# board.net
KiCad netlist of a schematic drawn in EAGLE
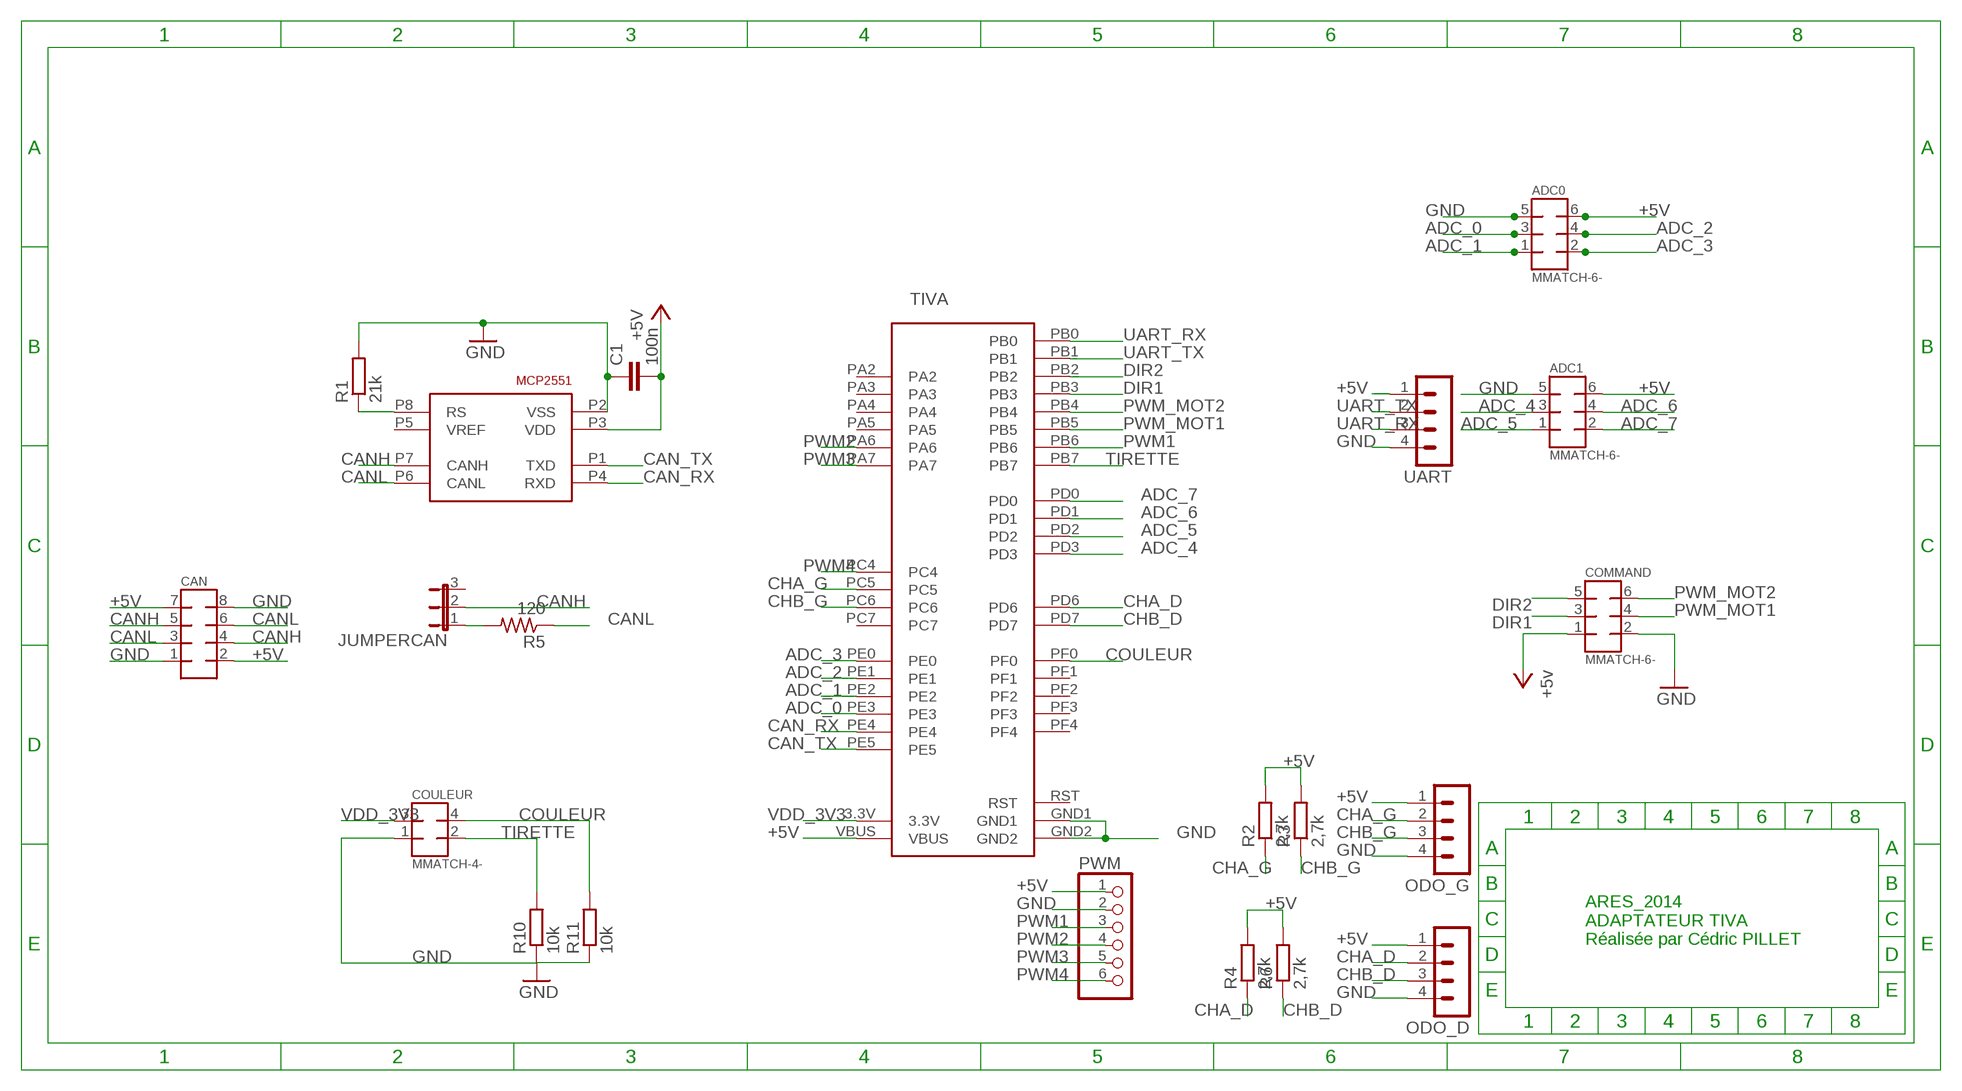
[diagram p0: schematic, sheet 1]

(export (version "E")
  (design (tool "Eeschema 10.0.6"))
  (components
    (comp (ref "ADC0")
      (value "MMATCH-6-")
      (footprint "eagle-import:AMP-215079-6")
      (libsource (lib "eagle-import") (part "MMATCH-6-"))
    )
    (comp (ref "ADC1")
      (value "MMATCH-6-")
      (footprint "eagle-import:AMP-215079-6")
      (libsource (lib "eagle-import") (part "MMATCH-6-"))
    )
    (comp (ref "C1")
      (value "100n")
      (footprint "eagle-import:C0805")
      (libsource (lib "eagle-import") (part "C-EUC0805"))
    )
    (comp (ref "CAN")
      (value "MMATCH-8-PTH")
      (footprint "eagle-import:AMP-215079-8")
      (libsource (lib "eagle-import") (part "MMATCH-8-PTH"))
    )
    (comp (ref "COMMAND")
      (value "MMATCH-6-")
      (footprint "eagle-import:AMP-215079-6")
      (libsource (lib "eagle-import") (part "MMATCH-6-"))
    )
    (comp (ref "COULEUR")
      (value "MMATCH-4-")
      (footprint "eagle-import:AMP-215079-4")
      (libsource (lib "eagle-import") (part "MMATCH-4-"))
    )
    (comp (ref "JUMPERCAN")
      (value "JP2W")
      (footprint "eagle-import:JP2W")
      (libsource (lib "eagle-import") (part "JP2W"))
    )
    (comp (ref "ODO_D")
      (value "MA04-1")
      (footprint "eagle-import:MA04-1")
      (libsource (lib "eagle-import") (part "MA04-1"))
    )
    (comp (ref "ODO_G")
      (value "MA04-1")
      (footprint "eagle-import:MA04-1")
      (libsource (lib "eagle-import") (part "MA04-1"))
    )
    (comp (ref "PWM")
      (value "PINHD-1X6/90")
      (footprint "eagle-import:1X06_90")
      (libsource (lib "eagle-import") (part "PINHD-1X6/90"))
    )
    (comp (ref "R1")
      (value "21k")
      (footprint "eagle-import:R0805")
      (libsource (lib "eagle-import") (part "R-EU_R0805"))
    )
    (comp (ref "R2")
      (value "2,7k")
      (footprint "eagle-import:R0805")
      (libsource (lib "eagle-import") (part "R-EU_R0805"))
    )
    (comp (ref "R3")
      (value "2,7k")
      (footprint "eagle-import:R0805")
      (libsource (lib "eagle-import") (part "R-EU_R0805"))
    )
    (comp (ref "R4")
      (value "2,7k")
      (footprint "eagle-import:R0805")
      (libsource (lib "eagle-import") (part "R-EU_R0805"))
    )
    (comp (ref "R5")
      (value "120")
      (footprint "eagle-import:M0805")
      (libsource (lib "eagle-import") (part "R-US_M0805"))
    )
    (comp (ref "R6")
      (value "2,7k")
      (footprint "eagle-import:R0805")
      (libsource (lib "eagle-import") (part "R-EU_R0805"))
    )
    (comp (ref "R10")
      (value "10k")
      (footprint "eagle-import:R0805")
      (libsource (lib "eagle-import") (part "R-EU_R0805"))
    )
    (comp (ref "R11")
      (value "10k")
      (footprint "eagle-import:R0805")
      (libsource (lib "eagle-import") (part "R-EU_R0805"))
    )
    (comp (ref "TIVA")
      (value "STELLARIS-LAUNCHPADSTELLARIS-LAUNCHPAD")
      (footprint "eagle-import:LAUNCHPAD-XL")
      (libsource (lib "eagle-import") (part "STELLARIS-LAUNCHPADSTELLARIS-LAUNCHPAD"))
    )
    (comp (ref "U$1")
      (value "MCP2551")
      (footprint "eagle-import:SOIC_8")
      (libsource (lib "eagle-import") (part "MCP2551"))
    )
    (comp (ref "UART")
      (value "MA04-1")
      (footprint "eagle-import:MA04-1")
      (libsource (lib "eagle-import") (part "MA04-1"))
    )
  )
  (nets
    (net (code "1") (name "+5V") (class "Default")
      (node (ref "ADC0") (pin "6") (pinfunction "8_6") (pintype "bidirectional"))
      (node (ref "ADC1") (pin "6") (pinfunction "8_6") (pintype "bidirectional"))
      (node (ref "C1") (pin "2") (pinfunction "2_2") (pintype "passive"))
      (node (ref "CAN") (pin "2") (pinfunction "2_2") (pintype "bidirectional"))
      (node (ref "CAN") (pin "7") (pinfunction "7_7") (pintype "bidirectional"))
      (node (ref "COMMAND") (pin "1") (pinfunction "3_1") (pintype "bidirectional"))
      (node (ref "ODO_D") (pin "1") (pinfunction "1_1") (pintype "passive"))
      (node (ref "ODO_G") (pin "1") (pinfunction "1_1") (pintype "passive"))
      (node (ref "PWM") (pin "1") (pinfunction "1_1") (pintype "passive"))
      (node (ref "R2") (pin "2") (pinfunction "2_2") (pintype "passive"))
      (node (ref "R3") (pin "2") (pinfunction "2_2") (pintype "passive"))
      (node (ref "R4") (pin "2") (pinfunction "2_2") (pintype "passive"))
      (node (ref "R6") (pin "2") (pinfunction "2_2") (pintype "passive"))
      (node (ref "TIVA") (pin "VBUS") (pinfunction "VBUS_VBUS") (pintype "power_in"))
      (node (ref "U$1") (pin "P3") (pinfunction "VDD_P3") (pintype "bidirectional"))
      (node (ref "UART") (pin "1") (pinfunction "1_1") (pintype "passive"))
    )
    (net (code "2") (name "/ADC_0") (class "Default")
      (node (ref "ADC0") (pin "3") (pinfunction "5_3") (pintype "bidirectional"))
      (node (ref "TIVA") (pin "PE3") (pinfunction "PE3_PE3") (pintype "bidirectional"))
    )
    (net (code "3") (name "/ADC_1") (class "Default")
      (node (ref "ADC0") (pin "1") (pinfunction "3_1") (pintype "bidirectional"))
      (node (ref "TIVA") (pin "PE2") (pinfunction "PE2_PE2") (pintype "bidirectional"))
    )
    (net (code "4") (name "/ADC_2") (class "Default")
      (node (ref "ADC0") (pin "4") (pinfunction "6_4") (pintype "bidirectional"))
      (node (ref "TIVA") (pin "PE1") (pinfunction "PE1_PE1") (pintype "bidirectional"))
    )
    (net (code "5") (name "/ADC_3") (class "Default")
      (node (ref "ADC0") (pin "2") (pinfunction "4_2") (pintype "bidirectional"))
      (node (ref "TIVA") (pin "PE0") (pinfunction "PE0_PE0") (pintype "bidirectional"))
    )
    (net (code "6") (name "/ADC_4") (class "Default")
      (node (ref "ADC1") (pin "3") (pinfunction "5_3") (pintype "bidirectional"))
      (node (ref "TIVA") (pin "PD3") (pinfunction "PD3_PD3") (pintype "bidirectional"))
    )
    (net (code "7") (name "/ADC_5") (class "Default")
      (node (ref "ADC1") (pin "1") (pinfunction "3_1") (pintype "bidirectional"))
      (node (ref "TIVA") (pin "PD2") (pinfunction "PD2_PD2") (pintype "bidirectional"))
    )
    (net (code "8") (name "/ADC_6") (class "Default")
      (node (ref "ADC1") (pin "4") (pinfunction "6_4") (pintype "bidirectional"))
      (node (ref "TIVA") (pin "PD1") (pinfunction "PD1_PD1") (pintype "bidirectional"))
    )
    (net (code "9") (name "/ADC_7") (class "Default")
      (node (ref "ADC1") (pin "2") (pinfunction "4_2") (pintype "bidirectional"))
      (node (ref "TIVA") (pin "PD0") (pinfunction "PD0_PD0") (pintype "bidirectional"))
    )
    (net (code "10") (name "/CANH") (class "Default")
      (node (ref "CAN") (pin "4") (pinfunction "4_4") (pintype "bidirectional"))
      (node (ref "CAN") (pin "5") (pinfunction "5_5") (pintype "bidirectional"))
      (node (ref "JUMPERCAN") (pin "2") (pinfunction "2_2") (pintype "passive"))
      (node (ref "U$1") (pin "P7") (pinfunction "CANH_P7") (pintype "bidirectional"))
    )
    (net (code "11") (name "/CANL") (class "Default")
      (node (ref "CAN") (pin "3") (pinfunction "3_3") (pintype "bidirectional"))
      (node (ref "CAN") (pin "6") (pinfunction "6_6") (pintype "bidirectional"))
      (node (ref "R5") (pin "1") (pinfunction "1_1") (pintype "passive"))
      (node (ref "U$1") (pin "P6") (pinfunction "CANL_P6") (pintype "bidirectional"))
    )
    (net (code "12") (name "/CAN_RX") (class "Default")
      (node (ref "TIVA") (pin "PE4") (pinfunction "PE4_PE4") (pintype "bidirectional"))
      (node (ref "U$1") (pin "P4") (pinfunction "RXD_P4") (pintype "bidirectional"))
    )
    (net (code "13") (name "/CAN_TX") (class "Default")
      (node (ref "TIVA") (pin "PE5") (pinfunction "PE5_PE5") (pintype "bidirectional"))
      (node (ref "U$1") (pin "P1") (pinfunction "TXD_P1") (pintype "bidirectional"))
    )
    (net (code "14") (name "/CHA_D") (class "Default")
      (node (ref "ODO_D") (pin "2") (pinfunction "2_2") (pintype "passive"))
      (node (ref "R4") (pin "1") (pinfunction "1_1") (pintype "passive"))
      (node (ref "TIVA") (pin "PD6") (pinfunction "PD6_PD6") (pintype "bidirectional"))
    )
    (net (code "15") (name "/CHA_G") (class "Default")
      (node (ref "ODO_G") (pin "2") (pinfunction "2_2") (pintype "passive"))
      (node (ref "R2") (pin "1") (pinfunction "1_1") (pintype "passive"))
      (node (ref "TIVA") (pin "PC5") (pinfunction "PC5_PC5") (pintype "bidirectional"))
    )
    (net (code "16") (name "/CHB_D") (class "Default")
      (node (ref "ODO_D") (pin "3") (pinfunction "3_3") (pintype "passive"))
      (node (ref "R6") (pin "1") (pinfunction "1_1") (pintype "passive"))
      (node (ref "TIVA") (pin "PD7") (pinfunction "PD7_PD7") (pintype "bidirectional"))
    )
    (net (code "17") (name "/CHB_G") (class "Default")
      (node (ref "ODO_G") (pin "3") (pinfunction "3_3") (pintype "passive"))
      (node (ref "R3") (pin "1") (pinfunction "1_1") (pintype "passive"))
      (node (ref "TIVA") (pin "PC6") (pinfunction "PC6_PC6") (pintype "bidirectional"))
    )
    (net (code "18") (name "/COULEUR") (class "Default")
      (node (ref "COULEUR") (pin "4") (pinfunction "8_4") (pintype "bidirectional"))
      (node (ref "R11") (pin "2") (pinfunction "2_2") (pintype "passive"))
      (node (ref "TIVA") (pin "PF0") (pinfunction "PF0_PF0") (pintype "bidirectional"))
    )
    (net (code "19") (name "/DIR1") (class "Default")
      (node (ref "COMMAND") (pin "3") (pinfunction "5_3") (pintype "bidirectional"))
      (node (ref "TIVA") (pin "PB3") (pinfunction "PB3_PB3") (pintype "bidirectional"))
    )
    (net (code "20") (name "/DIR2") (class "Default")
      (node (ref "COMMAND") (pin "5") (pinfunction "7_5") (pintype "bidirectional"))
      (node (ref "TIVA") (pin "PB2") (pinfunction "PB2_PB2") (pintype "bidirectional"))
    )
    (net (code "21") (name "/PWM1") (class "Default")
      (node (ref "PWM") (pin "3") (pinfunction "3_3") (pintype "passive"))
      (node (ref "TIVA") (pin "PB6") (pinfunction "PB6_PB6") (pintype "bidirectional"))
    )
    (net (code "22") (name "/PWM2") (class "Default")
      (node (ref "PWM") (pin "4") (pinfunction "4_4") (pintype "passive"))
      (node (ref "TIVA") (pin "PA6") (pinfunction "PA6_PA6") (pintype "bidirectional"))
    )
    (net (code "23") (name "/PWM3") (class "Default")
      (node (ref "PWM") (pin "5") (pinfunction "5_5") (pintype "passive"))
      (node (ref "TIVA") (pin "PA7") (pinfunction "PA7_PA7") (pintype "bidirectional"))
    )
    (net (code "24") (name "/PWM4") (class "Default")
      (node (ref "PWM") (pin "6") (pinfunction "6_6") (pintype "passive"))
      (node (ref "TIVA") (pin "PC4") (pinfunction "PC4_PC4") (pintype "bidirectional"))
    )
    (net (code "25") (name "/PWM_MOT1") (class "Default")
      (node (ref "COMMAND") (pin "4") (pinfunction "6_4") (pintype "bidirectional"))
      (node (ref "TIVA") (pin "PB5") (pinfunction "PB5_PB5") (pintype "bidirectional"))
    )
    (net (code "26") (name "/PWM_MOT2") (class "Default")
      (node (ref "COMMAND") (pin "6") (pinfunction "8_6") (pintype "bidirectional"))
      (node (ref "TIVA") (pin "PB4") (pinfunction "PB4_PB4") (pintype "bidirectional"))
    )
    (net (code "27") (name "/RST") (class "Default")
      (node (ref "TIVA") (pin "RST") (pinfunction "RST_RST") (pintype "power_in"))
    )
    (net (code "28") (name "/TIRETTE") (class "Default")
      (node (ref "COULEUR") (pin "2") (pinfunction "6_2") (pintype "bidirectional"))
      (node (ref "R10") (pin "2") (pinfunction "2_2") (pintype "passive"))
      (node (ref "TIVA") (pin "PB7") (pinfunction "PB7_PB7") (pintype "bidirectional"))
    )
    (net (code "29") (name "/UART_RX") (class "Default")
      (node (ref "TIVA") (pin "PB0") (pinfunction "PB0_PB0") (pintype "bidirectional"))
      (node (ref "UART") (pin "3") (pinfunction "3_3") (pintype "passive"))
    )
    (net (code "30") (name "/UART_TX") (class "Default")
      (node (ref "TIVA") (pin "PB1") (pinfunction "PB1_PB1") (pintype "bidirectional"))
      (node (ref "UART") (pin "2") (pinfunction "2_2") (pintype "passive"))
    )
    (net (code "31") (name "/VDD_3V3") (class "Default")
      (node (ref "COULEUR") (pin "3") (pinfunction "7_3") (pintype "bidirectional"))
      (node (ref "TIVA") (pin "3.3V") (pinfunction "3.3V_3.3V") (pintype "power_in"))
    )
    (net (code "32") (name "GND") (class "Default")
      (node (ref "ADC0") (pin "5") (pinfunction "7_5") (pintype "bidirectional"))
      (node (ref "ADC1") (pin "5") (pinfunction "7_5") (pintype "bidirectional"))
      (node (ref "C1") (pin "1") (pinfunction "1_1") (pintype "passive"))
      (node (ref "CAN") (pin "1") (pinfunction "1_1") (pintype "bidirectional"))
      (node (ref "CAN") (pin "8") (pinfunction "8_8") (pintype "bidirectional"))
      (node (ref "COMMAND") (pin "2") (pinfunction "4_2") (pintype "bidirectional"))
      (node (ref "COULEUR") (pin "1") (pinfunction "5_1") (pintype "bidirectional"))
      (node (ref "ODO_D") (pin "4") (pinfunction "4_4") (pintype "passive"))
      (node (ref "ODO_G") (pin "4") (pinfunction "4_4") (pintype "passive"))
      (node (ref "PWM") (pin "2") (pinfunction "2_2") (pintype "passive"))
      (node (ref "R1") (pin "2") (pinfunction "2_2") (pintype "passive"))
      (node (ref "R10") (pin "1") (pinfunction "1_1") (pintype "passive"))
      (node (ref "R11") (pin "1") (pinfunction "1_1") (pintype "passive"))
      (node (ref "TIVA") (pin "GND1") (pinfunction "GND1_GND1") (pintype "bidirectional"))
      (node (ref "TIVA") (pin "GND2") (pinfunction "GND2_GND2") (pintype "power_in"))
      (node (ref "U$1") (pin "P2") (pinfunction "VSS_P2") (pintype "bidirectional"))
      (node (ref "UART") (pin "4") (pinfunction "4_4") (pintype "passive"))
    )
    (net (code "33") (name "Net-(JUMPERCAN-Pad1)") (class "Default")
      (node (ref "JUMPERCAN") (pin "1") (pinfunction "1_1") (pintype "passive"))
      (node (ref "R5") (pin "2") (pinfunction "2_2") (pintype "passive"))
    )
    (net (code "34") (name "Net-(U$1-RS)") (class "Default")
      (node (ref "R1") (pin "1") (pinfunction "1_1") (pintype "passive"))
      (node (ref "U$1") (pin "P8") (pinfunction "RS_P8") (pintype "bidirectional"))
    )
    (net (code "35") (name "unconnected-(JUMPERCAN-Pad3)") (class "Default")
      (node (ref "JUMPERCAN") (pin "3") (pinfunction "3_3") (pintype "passive"))
    )
    (net (code "36") (name "unconnected-(TIVA-PadPA2)") (class "Default")
      (node (ref "TIVA") (pin "PA2") (pinfunction "PA2_PA2") (pintype "bidirectional"))
    )
    (net (code "37") (name "unconnected-(TIVA-PadPA3)") (class "Default")
      (node (ref "TIVA") (pin "PA3") (pinfunction "PA3_PA3") (pintype "bidirectional"))
    )
    (net (code "38") (name "unconnected-(TIVA-PadPA4)") (class "Default")
      (node (ref "TIVA") (pin "PA4") (pinfunction "PA4_PA4") (pintype "bidirectional"))
    )
    (net (code "39") (name "unconnected-(TIVA-PadPA5)") (class "Default")
      (node (ref "TIVA") (pin "PA5") (pinfunction "PA5_PA5") (pintype "bidirectional"))
    )
    (net (code "40") (name "unconnected-(TIVA-PadPC7)") (class "Default")
      (node (ref "TIVA") (pin "PC7") (pinfunction "PC7_PC7") (pintype "bidirectional"))
    )
    (net (code "41") (name "unconnected-(TIVA-PadPF1)") (class "Default")
      (node (ref "TIVA") (pin "PF1") (pinfunction "PF1_PF1") (pintype "bidirectional"))
    )
    (net (code "42") (name "unconnected-(TIVA-PadPF2)") (class "Default")
      (node (ref "TIVA") (pin "PF2") (pinfunction "PF2_PF2") (pintype "bidirectional"))
    )
    (net (code "43") (name "unconnected-(TIVA-PadPF3)") (class "Default")
      (node (ref "TIVA") (pin "PF3") (pinfunction "PF3_PF3") (pintype "bidirectional"))
    )
    (net (code "44") (name "unconnected-(TIVA-PadPF4)") (class "Default")
      (node (ref "TIVA") (pin "PF4") (pinfunction "PF4_PF4") (pintype "bidirectional"))
    )
    (net (code "45") (name "unconnected-(U$1-VREF-PadP5)") (class "Default")
      (node (ref "U$1") (pin "P5") (pinfunction "VREF_P5") (pintype "bidirectional"))
    )
  )
)
